# SPI_Expander_MCP23S09.net
KiCad netlist of a schematic drawn in Altium Designer
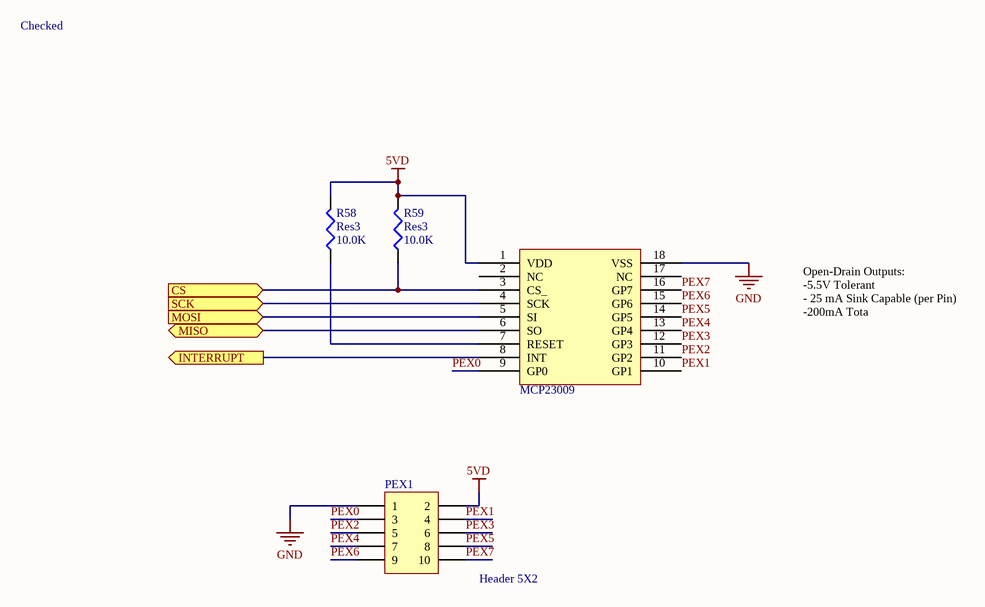
[diagram p0: SPI_Expander_MCP23S09.SchDoc]

(export (version "E")
  (design (tool "Eeschema 10.0.6"))
  (components
    (comp (ref "IC1") (value "MCP23009") (footprint "MCP23009") (libsource (lib "Crystal") (part "MCP23009")))
    (comp (ref "PEX1")
      (value "Header 5X2")
      (footprint "HDR2X5")
      (description "Header, 5-Pin, Dual row")
      (fields (field (name "PUBLISHER") "Altium Limited"))
      (libsource (lib "Miscellaneous Connectors") (part "Header 5X2"))
    )
    (comp (ref "R58")
      (value "Res3")
      (footprint "RESC2112X05M")
      (description "RES SMD 10.0K OHM 1% 1/8W 0805")
      (fields (field (name "ALTIUM_VALUE") "10.0K") (field (name "MPN") "CRCW080510K0FKEA"))
      (libsource (lib "esd_library") (part "Resistor_10.0K"))
    )
    (comp (ref "R59")
      (value "Res3")
      (footprint "RESC2112X05M")
      (description "RES SMD 10.0K OHM 1% 1/8W 0805")
      (fields (field (name "ALTIUM_VALUE") "10.0K") (field (name "MPN") "CRCW080510K0FKEA"))
      (libsource (lib "esd_library") (part "Resistor_10.0K"))
    )
  )
  (nets
    (net (code "1") (name "/CS") (class "Default")
      (node (ref "IC1") (pin "3") (pinfunction "CS__3") (pintype "passive"))
      (node (ref "R59") (pin "1") (pinfunction "1_1") (pintype "passive"))
    )
    (net (code "2") (name "/INTERRUPT") (class "Default")
      (node (ref "IC1") (pin "8") (pinfunction "INT_8") (pintype "passive"))
    )
    (net (code "3") (name "/MISO") (class "Default")
      (node (ref "IC1") (pin "6") (pinfunction "SO_6") (pintype "passive"))
    )
    (net (code "4") (name "/MOSI") (class "Default")
      (node (ref "IC1") (pin "5") (pinfunction "SI_5") (pintype "passive"))
    )
    (net (code "5") (name "/PEX0") (class "Default")
      (node (ref "IC1") (pin "9") (pinfunction "GP0_9") (pintype "passive"))
      (node (ref "PEX1") (pin "3") (pinfunction "3_3") (pintype "passive"))
    )
    (net (code "6") (name "/PEX1") (class "Default")
      (node (ref "IC1") (pin "10") (pinfunction "GP1_10") (pintype "passive"))
      (node (ref "PEX1") (pin "4") (pinfunction "4_4") (pintype "passive"))
    )
    (net (code "7") (name "/PEX2") (class "Default")
      (node (ref "IC1") (pin "11") (pinfunction "GP2_11") (pintype "passive"))
      (node (ref "PEX1") (pin "5") (pinfunction "5_5") (pintype "passive"))
    )
    (net (code "8") (name "/PEX3") (class "Default")
      (node (ref "IC1") (pin "12") (pinfunction "GP3_12") (pintype "passive"))
      (node (ref "PEX1") (pin "6") (pinfunction "6_6") (pintype "passive"))
    )
    (net (code "9") (name "/PEX4") (class "Default")
      (node (ref "IC1") (pin "13") (pinfunction "GP4_13") (pintype "passive"))
      (node (ref "PEX1") (pin "7") (pinfunction "7_7") (pintype "passive"))
    )
    (net (code "10") (name "/PEX5") (class "Default")
      (node (ref "IC1") (pin "14") (pinfunction "GP5_14") (pintype "passive"))
      (node (ref "PEX1") (pin "8") (pinfunction "8_8") (pintype "passive"))
    )
    (net (code "11") (name "/PEX6") (class "Default")
      (node (ref "IC1") (pin "15") (pinfunction "GP6_15") (pintype "passive"))
      (node (ref "PEX1") (pin "9") (pinfunction "9_9") (pintype "passive"))
    )
    (net (code "12") (name "/PEX7") (class "Default")
      (node (ref "IC1") (pin "16") (pinfunction "GP7_16") (pintype "passive"))
      (node (ref "PEX1") (pin "10") (pinfunction "10_10") (pintype "passive"))
    )
    (net (code "13") (name "/SCK") (class "Default")
      (node (ref "IC1") (pin "4") (pinfunction "SCK_4") (pintype "passive"))
    )
    (net (code "14") (name "5VD") (class "Default")
      (node (ref "IC1") (pin "1") (pinfunction "VDD_1") (pintype "passive"))
      (node (ref "PEX1") (pin "2") (pinfunction "2_2") (pintype "passive"))
      (node (ref "R58") (pin "2") (pinfunction "2_2") (pintype "passive"))
      (node (ref "R59") (pin "2") (pinfunction "2_2") (pintype "passive"))
    )
    (net (code "15") (name "GND") (class "Default")
      (node (ref "IC1") (pin "18") (pinfunction "VSS_18") (pintype "passive"))
      (node (ref "PEX1") (pin "1") (pinfunction "1_1") (pintype "passive"))
    )
    (net (code "16") (name "Net-(IC1-RESET)") (class "Default")
      (node (ref "IC1") (pin "7") (pinfunction "RESET_7") (pintype "passive"))
      (node (ref "R58") (pin "1") (pinfunction "1_1") (pintype "passive"))
    )
    (net (code "17") (name "unconnected-(IC1-NC-Pad2)") (class "Default")
      (node (ref "IC1") (pin "2") (pinfunction "NC_2") (pintype "passive"))
    )
    (net (code "18") (name "unconnected-(IC1-NC-Pad17)") (class "Default")
      (node (ref "IC1") (pin "17") (pinfunction "NC_17") (pintype "passive"))
    )
  )
)
